# Header_Pinout.net
KiCad netlist of a schematic drawn in Altium Designer
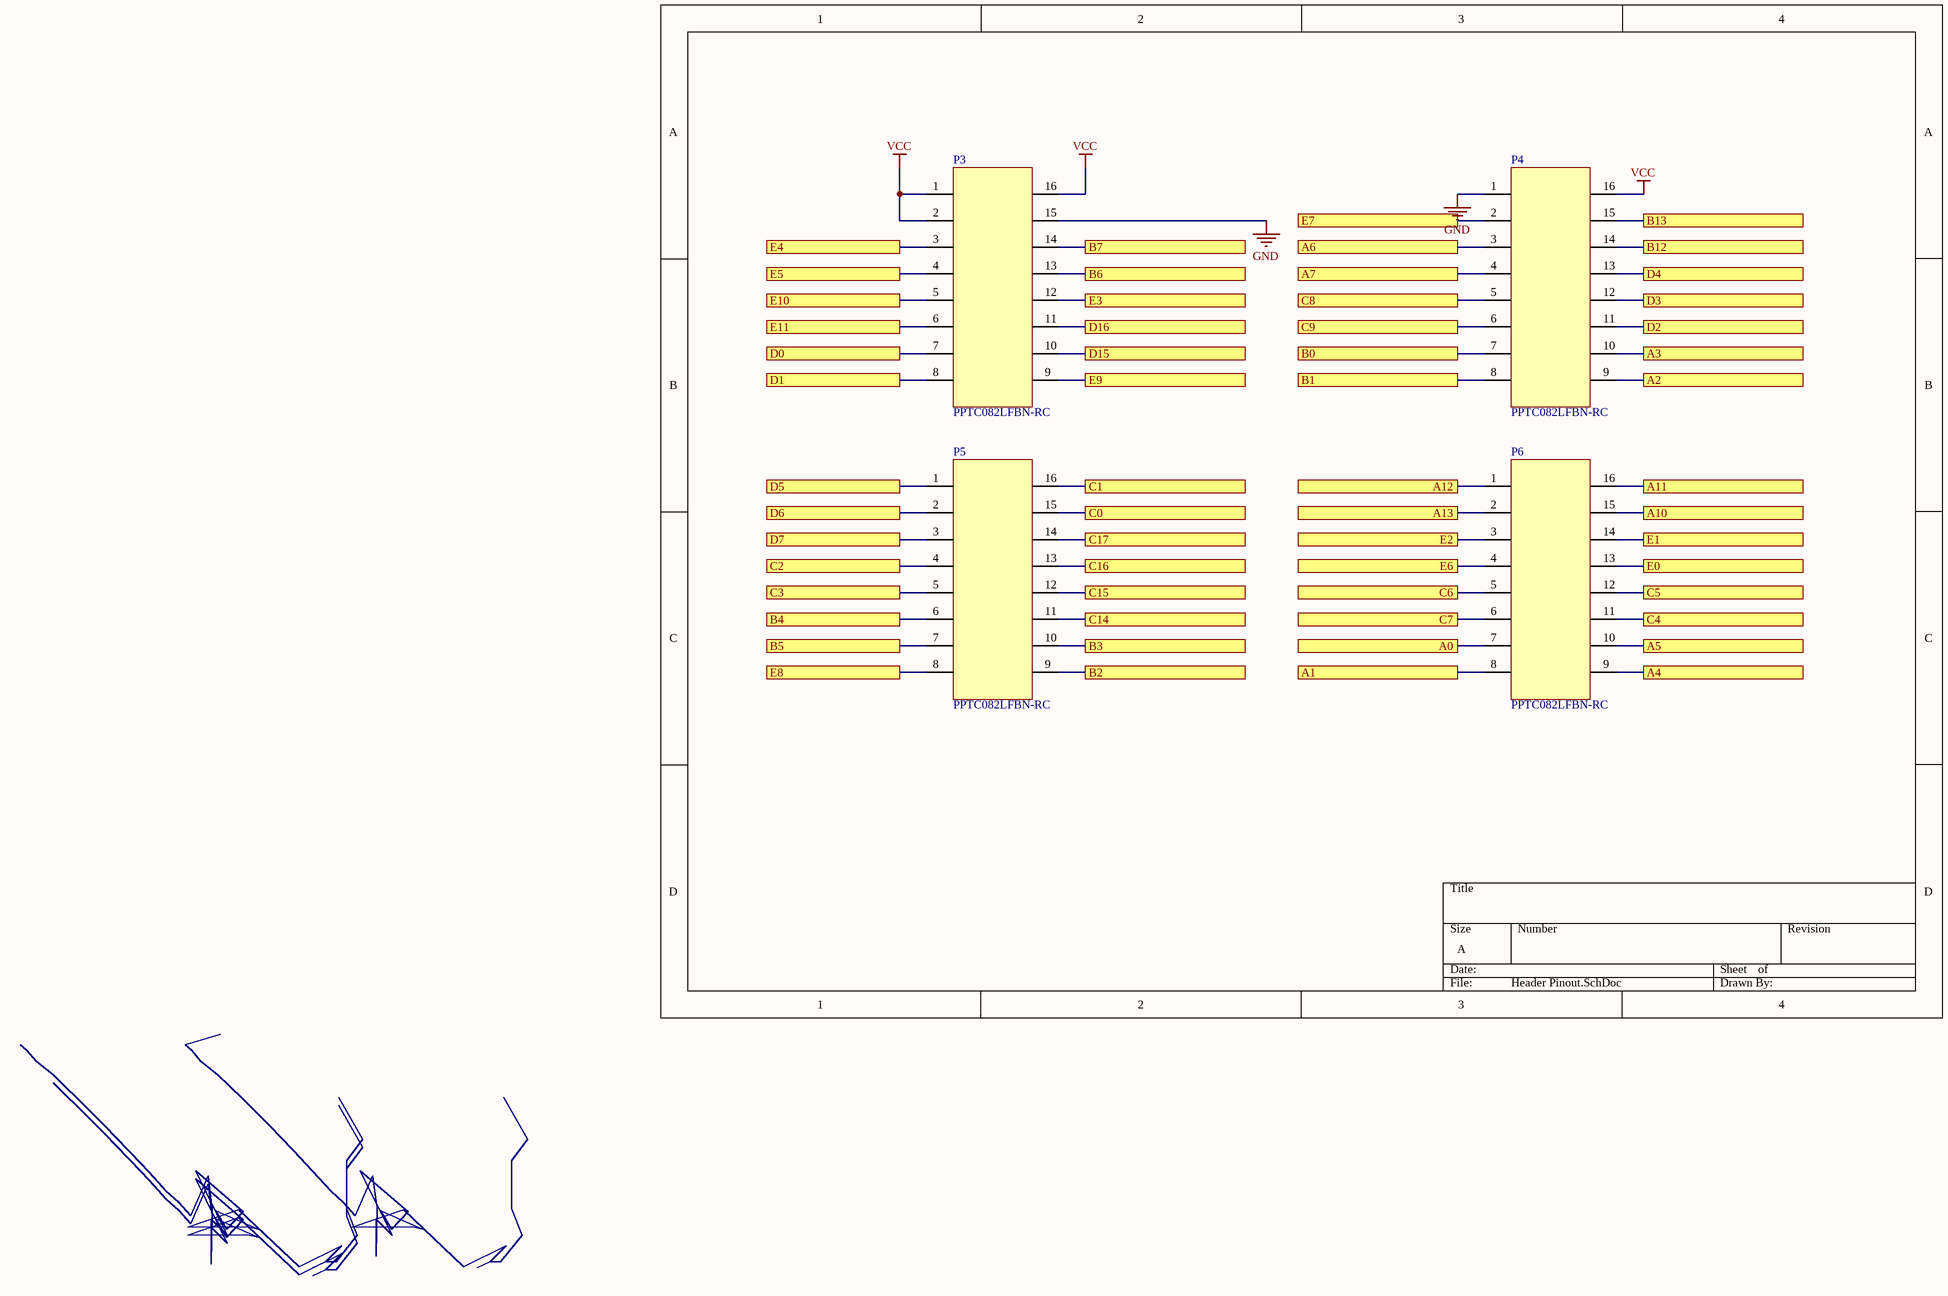
[diagram p0: Header Pinout.SchDoc]

(export (version "E")
  (design (tool "Eeschema 10.0.6"))
  (components
    (comp (ref "P3")
      (value "PPTC082LFBN-RC")
      (footprint "PPTC082LFBN-RC")
      (description "2x8 female header")
      (fields (field (name "CREATED_BY") "Austin") (field (name "UPDATED_BY") "Null"))
      (libsource (lib "Altium-Lib") (part "PPTC082LFBN-RC"))
    )
    (comp (ref "P4")
      (value "PPTC082LFBN-RC")
      (footprint "PPTC082LFBN-RC")
      (description "2x8 female header")
      (fields (field (name "CREATED_BY") "Austin") (field (name "UPDATED_BY") "Null"))
      (libsource (lib "Altium-Lib") (part "PPTC082LFBN-RC"))
    )
    (comp (ref "P5")
      (value "PPTC082LFBN-RC")
      (footprint "PPTC082LFBN-RC")
      (description "2x8 female header")
      (fields (field (name "CREATED_BY") "Austin") (field (name "UPDATED_BY") "Null"))
      (libsource (lib "Altium-Lib") (part "PPTC082LFBN-RC"))
    )
    (comp (ref "P6")
      (value "PPTC082LFBN-RC")
      (footprint "PPTC082LFBN-RC")
      (description "2x8 female header")
      (fields (field (name "CREATED_BY") "Austin") (field (name "UPDATED_BY") "Null"))
      (libsource (lib "Altium-Lib") (part "PPTC082LFBN-RC"))
    )
  )
  (nets
    (net (code "1") (name "/A0") (class "Default")
      (node (ref "P6") (pin "7") (pinfunction "7_7") (pintype "passive"))
    )
    (net (code "2") (name "/A1") (class "Default")
      (node (ref "P6") (pin "8") (pinfunction "8_8") (pintype "passive"))
    )
    (net (code "3") (name "/A2") (class "Default")
      (node (ref "P4") (pin "9") (pinfunction "9_9") (pintype "passive"))
    )
    (net (code "4") (name "/A3") (class "Default")
      (node (ref "P4") (pin "10") (pinfunction "10_10") (pintype "passive"))
    )
    (net (code "5") (name "/A4") (class "Default")
      (node (ref "P6") (pin "9") (pinfunction "9_9") (pintype "passive"))
    )
    (net (code "6") (name "/A5") (class "Default")
      (node (ref "P6") (pin "10") (pinfunction "10_10") (pintype "passive"))
    )
    (net (code "7") (name "/A6") (class "Default")
      (node (ref "P4") (pin "3") (pinfunction "3_3") (pintype "passive"))
    )
    (net (code "8") (name "/A7") (class "Default")
      (node (ref "P4") (pin "4") (pinfunction "4_4") (pintype "passive"))
    )
    (net (code "9") (name "/A10") (class "Default")
      (node (ref "P6") (pin "15") (pinfunction "15_15") (pintype "passive"))
    )
    (net (code "10") (name "/A11") (class "Default")
      (node (ref "P6") (pin "16") (pinfunction "16_16") (pintype "passive"))
    )
    (net (code "11") (name "/A12") (class "Default")
      (node (ref "P6") (pin "1") (pinfunction "1_1") (pintype "passive"))
    )
    (net (code "12") (name "/A13") (class "Default")
      (node (ref "P6") (pin "2") (pinfunction "2_2") (pintype "passive"))
    )
    (net (code "13") (name "/B0") (class "Default")
      (node (ref "P4") (pin "7") (pinfunction "7_7") (pintype "passive"))
    )
    (net (code "14") (name "/B1") (class "Default")
      (node (ref "P4") (pin "8") (pinfunction "8_8") (pintype "passive"))
    )
    (net (code "15") (name "/B2") (class "Default")
      (node (ref "P5") (pin "9") (pinfunction "9_9") (pintype "passive"))
    )
    (net (code "16") (name "/B3") (class "Default")
      (node (ref "P5") (pin "10") (pinfunction "10_10") (pintype "passive"))
    )
    (net (code "17") (name "/B4") (class "Default")
      (node (ref "P5") (pin "6") (pinfunction "6_6") (pintype "passive"))
    )
    (net (code "18") (name "/B5") (class "Default")
      (node (ref "P5") (pin "7") (pinfunction "7_7") (pintype "passive"))
    )
    (net (code "19") (name "/B6") (class "Default")
      (node (ref "P3") (pin "13") (pinfunction "13_13") (pintype "passive"))
    )
    (net (code "20") (name "/B7") (class "Default")
      (node (ref "P3") (pin "14") (pinfunction "14_14") (pintype "passive"))
    )
    (net (code "21") (name "/B12") (class "Default")
      (node (ref "P4") (pin "14") (pinfunction "14_14") (pintype "passive"))
    )
    (net (code "22") (name "/B13") (class "Default")
      (node (ref "P4") (pin "15") (pinfunction "15_15") (pintype "passive"))
    )
    (net (code "23") (name "/C0") (class "Default")
      (node (ref "P5") (pin "15") (pinfunction "15_15") (pintype "passive"))
    )
    (net (code "24") (name "/C1") (class "Default")
      (node (ref "P5") (pin "16") (pinfunction "16_16") (pintype "passive"))
    )
    (net (code "25") (name "/C2") (class "Default")
      (node (ref "P5") (pin "4") (pinfunction "4_4") (pintype "passive"))
    )
    (net (code "26") (name "/C3") (class "Default")
      (node (ref "P5") (pin "5") (pinfunction "5_5") (pintype "passive"))
    )
    (net (code "27") (name "/C4") (class "Default")
      (node (ref "P6") (pin "11") (pinfunction "11_11") (pintype "passive"))
    )
    (net (code "28") (name "/C5") (class "Default")
      (node (ref "P6") (pin "12") (pinfunction "12_12") (pintype "passive"))
    )
    (net (code "29") (name "/C6") (class "Default")
      (node (ref "P6") (pin "5") (pinfunction "5_5") (pintype "passive"))
    )
    (net (code "30") (name "/C7") (class "Default")
      (node (ref "P6") (pin "6") (pinfunction "6_6") (pintype "passive"))
    )
    (net (code "31") (name "/C8") (class "Default")
      (node (ref "P4") (pin "5") (pinfunction "5_5") (pintype "passive"))
    )
    (net (code "32") (name "/C9") (class "Default")
      (node (ref "P4") (pin "6") (pinfunction "6_6") (pintype "passive"))
    )
    (net (code "33") (name "/C14") (class "Default")
      (node (ref "P5") (pin "11") (pinfunction "11_11") (pintype "passive"))
    )
    (net (code "34") (name "/C15") (class "Default")
      (node (ref "P5") (pin "12") (pinfunction "12_12") (pintype "passive"))
    )
    (net (code "35") (name "/C16") (class "Default")
      (node (ref "P5") (pin "13") (pinfunction "13_13") (pintype "passive"))
    )
    (net (code "36") (name "/C17") (class "Default")
      (node (ref "P5") (pin "14") (pinfunction "14_14") (pintype "passive"))
    )
    (net (code "37") (name "/D0") (class "Default")
      (node (ref "P3") (pin "7") (pinfunction "7_7") (pintype "passive"))
    )
    (net (code "38") (name "/D1") (class "Default")
      (node (ref "P3") (pin "8") (pinfunction "8_8") (pintype "passive"))
    )
    (net (code "39") (name "/D2") (class "Default")
      (node (ref "P4") (pin "11") (pinfunction "11_11") (pintype "passive"))
    )
    (net (code "40") (name "/D3") (class "Default")
      (node (ref "P4") (pin "12") (pinfunction "12_12") (pintype "passive"))
    )
    (net (code "41") (name "/D4") (class "Default")
      (node (ref "P4") (pin "13") (pinfunction "13_13") (pintype "passive"))
    )
    (net (code "42") (name "/D5") (class "Default")
      (node (ref "P5") (pin "1") (pinfunction "1_1") (pintype "passive"))
    )
    (net (code "43") (name "/D6") (class "Default")
      (node (ref "P5") (pin "2") (pinfunction "2_2") (pintype "passive"))
    )
    (net (code "44") (name "/D7") (class "Default")
      (node (ref "P5") (pin "3") (pinfunction "3_3") (pintype "passive"))
    )
    (net (code "45") (name "/D15") (class "Default")
      (node (ref "P3") (pin "10") (pinfunction "10_10") (pintype "passive"))
    )
    (net (code "46") (name "/D16") (class "Default")
      (node (ref "P3") (pin "11") (pinfunction "11_11") (pintype "passive"))
    )
    (net (code "47") (name "/E0") (class "Default")
      (node (ref "P6") (pin "13") (pinfunction "13_13") (pintype "passive"))
    )
    (net (code "48") (name "/E1") (class "Default")
      (node (ref "P6") (pin "14") (pinfunction "14_14") (pintype "passive"))
    )
    (net (code "49") (name "/E2") (class "Default")
      (node (ref "P6") (pin "3") (pinfunction "3_3") (pintype "passive"))
    )
    (net (code "50") (name "/E3") (class "Default")
      (node (ref "P3") (pin "12") (pinfunction "12_12") (pintype "passive"))
    )
    (net (code "51") (name "/E4") (class "Default")
      (node (ref "P3") (pin "3") (pinfunction "3_3") (pintype "passive"))
    )
    (net (code "52") (name "/E5") (class "Default")
      (node (ref "P3") (pin "4") (pinfunction "4_4") (pintype "passive"))
    )
    (net (code "53") (name "/E6") (class "Default")
      (node (ref "P6") (pin "4") (pinfunction "4_4") (pintype "passive"))
    )
    (net (code "54") (name "/E7") (class "Default")
      (node (ref "P4") (pin "2") (pinfunction "2_2") (pintype "passive"))
    )
    (net (code "55") (name "/E8") (class "Default")
      (node (ref "P5") (pin "8") (pinfunction "8_8") (pintype "passive"))
    )
    (net (code "56") (name "/E9") (class "Default")
      (node (ref "P3") (pin "9") (pinfunction "9_9") (pintype "passive"))
    )
    (net (code "57") (name "/E10") (class "Default")
      (node (ref "P3") (pin "5") (pinfunction "5_5") (pintype "passive"))
    )
    (net (code "58") (name "/E11") (class "Default")
      (node (ref "P3") (pin "6") (pinfunction "6_6") (pintype "passive"))
    )
    (net (code "59") (name "GND") (class "Default")
      (node (ref "P3") (pin "15") (pinfunction "15_15") (pintype "passive"))
      (node (ref "P4") (pin "1") (pinfunction "1_1") (pintype "passive"))
    )
    (net (code "60") (name "VCC") (class "Default")
      (node (ref "P3") (pin "1") (pinfunction "1_1") (pintype "passive"))
      (node (ref "P3") (pin "16") (pinfunction "16_16") (pintype "passive"))
      (node (ref "P3") (pin "2") (pinfunction "2_2") (pintype "passive"))
      (node (ref "P4") (pin "16") (pinfunction "16_16") (pintype "passive"))
    )
  )
)
